# main1.net
KiCad netlist of a schematic drawn in EAGLE
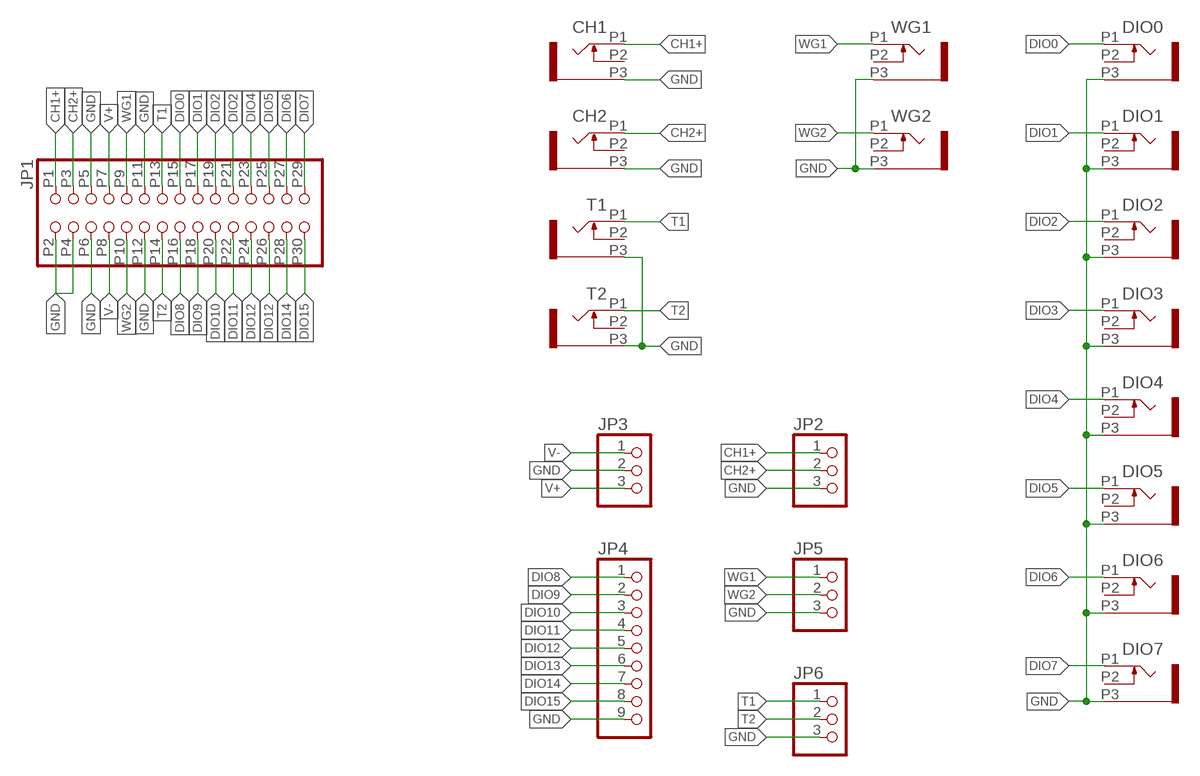
[diagram p0: schematic, sheet 1]

(export (version "E")
  (design (tool "Eeschema 10.0.6"))
  (components
    (comp (ref "CH1")
      (value "THONKICONN")
      (footprint "eagle-import:WQP-PJ301M-12_JACK")
      (libsource (lib "eagle-import") (part "THONKICONN"))
    )
    (comp (ref "CH2")
      (value "THONKICONN")
      (footprint "eagle-import:WQP-PJ301M-12_JACK")
      (libsource (lib "eagle-import") (part "THONKICONN"))
    )
    (comp (ref "DIO0")
      (value "THONKICONN")
      (footprint "eagle-import:WQP-PJ301M-12_JACK")
      (libsource (lib "eagle-import") (part "THONKICONN"))
    )
    (comp (ref "DIO1")
      (value "THONKICONN")
      (footprint "eagle-import:WQP-PJ301M-12_JACK")
      (libsource (lib "eagle-import") (part "THONKICONN"))
    )
    (comp (ref "DIO2")
      (value "THONKICONN")
      (footprint "eagle-import:WQP-PJ301M-12_JACK")
      (libsource (lib "eagle-import") (part "THONKICONN"))
    )
    (comp (ref "DIO3")
      (value "THONKICONN")
      (footprint "eagle-import:WQP-PJ301M-12_JACK")
      (libsource (lib "eagle-import") (part "THONKICONN"))
    )
    (comp (ref "DIO4")
      (value "THONKICONN")
      (footprint "eagle-import:WQP-PJ301M-12_JACK")
      (libsource (lib "eagle-import") (part "THONKICONN"))
    )
    (comp (ref "DIO5")
      (value "THONKICONN")
      (footprint "eagle-import:WQP-PJ301M-12_JACK")
      (libsource (lib "eagle-import") (part "THONKICONN"))
    )
    (comp (ref "DIO6")
      (value "THONKICONN")
      (footprint "eagle-import:WQP-PJ301M-12_JACK")
      (libsource (lib "eagle-import") (part "THONKICONN"))
    )
    (comp (ref "DIO7")
      (value "THONKICONN")
      (footprint "eagle-import:WQP-PJ301M-12_JACK")
      (libsource (lib "eagle-import") (part "THONKICONN"))
    )
    (comp (ref "JP1")
      (value "PINHD-2X15")
      (footprint "eagle-import:2X15_EDGE")
      (libsource (lib "eagle-import") (part "PINHD-2X15"))
    )
    (comp (ref "JP2")
      (value "PINHD-1X3/OCT")
      (footprint "eagle-import:1X03_OCT")
      (libsource (lib "eagle-import") (part "PINHD-1X3/OCT"))
    )
    (comp (ref "JP3")
      (value "PINHD-1X3/OCT")
      (footprint "eagle-import:1X03_OCT")
      (libsource (lib "eagle-import") (part "PINHD-1X3/OCT"))
    )
    (comp (ref "JP4")
      (value "PINHD-1X9/OCT")
      (footprint "eagle-import:1X09_OCT")
      (libsource (lib "eagle-import") (part "PINHD-1X9/OCT"))
    )
    (comp (ref "JP5")
      (value "PINHD-1X3/OCT")
      (footprint "eagle-import:1X03_OCT")
      (libsource (lib "eagle-import") (part "PINHD-1X3/OCT"))
    )
    (comp (ref "JP6")
      (value "PINHD-1X3/OCT")
      (footprint "eagle-import:1X03_OCT")
      (libsource (lib "eagle-import") (part "PINHD-1X3/OCT"))
    )
    (comp (ref "T1")
      (value "THONKICONN")
      (footprint "eagle-import:WQP-PJ301M-12_JACK")
      (libsource (lib "eagle-import") (part "THONKICONN"))
    )
    (comp (ref "T2")
      (value "THONKICONN")
      (footprint "eagle-import:WQP-PJ301M-12_JACK")
      (libsource (lib "eagle-import") (part "THONKICONN"))
    )
    (comp (ref "WG1")
      (value "THONKICONN")
      (footprint "eagle-import:WQP-PJ301M-12_JACK")
      (libsource (lib "eagle-import") (part "THONKICONN"))
    )
    (comp (ref "WG2")
      (value "THONKICONN")
      (footprint "eagle-import:WQP-PJ301M-12_JACK")
      (libsource (lib "eagle-import") (part "THONKICONN"))
    )
  )
  (nets
    (net (code "1") (name "CH1+") (class "Default")
      (node (ref "CH1") (pin "P1") (pinfunction "2_P1") (pintype "passive"))
      (node (ref "JP1") (pin "P1") (pinfunction "1_P1") (pintype "passive"))
      (node (ref "JP2") (pin "1") (pinfunction "1_1") (pintype "passive"))
    )
    (net (code "2") (name "CH2+") (class "Default")
      (node (ref "CH2") (pin "P1") (pinfunction "2_P1") (pintype "passive"))
      (node (ref "JP1") (pin "P3") (pinfunction "3_P3") (pintype "passive"))
      (node (ref "JP2") (pin "2") (pinfunction "2_2") (pintype "passive"))
    )
    (net (code "3") (name "DIO0") (class "Default")
      (node (ref "DIO0") (pin "P1") (pinfunction "2_P1") (pintype "passive"))
      (node (ref "JP1") (pin "P15") (pinfunction "15_P15") (pintype "passive"))
    )
    (net (code "4") (name "DIO1") (class "Default")
      (node (ref "DIO1") (pin "P1") (pinfunction "2_P1") (pintype "passive"))
      (node (ref "JP1") (pin "P17") (pinfunction "17_P17") (pintype "passive"))
    )
    (net (code "5") (name "DIO2") (class "Default")
      (node (ref "DIO2") (pin "P1") (pinfunction "2_P1") (pintype "passive"))
      (node (ref "JP1") (pin "P19") (pinfunction "19_P19") (pintype "passive"))
    )
    (net (code "6") (name "DIO3") (class "Default")
      (node (ref "DIO3") (pin "P1") (pinfunction "2_P1") (pintype "passive"))
      (node (ref "JP1") (pin "P21") (pinfunction "21_P21") (pintype "passive"))
    )
    (net (code "7") (name "DIO4") (class "Default")
      (node (ref "DIO4") (pin "P1") (pinfunction "2_P1") (pintype "passive"))
      (node (ref "JP1") (pin "P23") (pinfunction "23_P23") (pintype "passive"))
    )
    (net (code "8") (name "DIO5") (class "Default")
      (node (ref "DIO5") (pin "P1") (pinfunction "2_P1") (pintype "passive"))
      (node (ref "JP1") (pin "P25") (pinfunction "25_P25") (pintype "passive"))
    )
    (net (code "9") (name "DIO6") (class "Default")
      (node (ref "DIO6") (pin "P1") (pinfunction "2_P1") (pintype "passive"))
      (node (ref "JP1") (pin "P27") (pinfunction "27_P27") (pintype "passive"))
    )
    (net (code "10") (name "DIO7") (class "Default")
      (node (ref "DIO7") (pin "P1") (pinfunction "2_P1") (pintype "passive"))
      (node (ref "JP1") (pin "P29") (pinfunction "29_P29") (pintype "passive"))
    )
    (net (code "11") (name "DIO8") (class "Default")
      (node (ref "JP1") (pin "P16") (pinfunction "16_P16") (pintype "passive"))
      (node (ref "JP4") (pin "1") (pinfunction "1_1") (pintype "passive"))
    )
    (net (code "12") (name "DIO9") (class "Default")
      (node (ref "JP1") (pin "P18") (pinfunction "18_P18") (pintype "passive"))
      (node (ref "JP4") (pin "2") (pinfunction "2_2") (pintype "passive"))
    )
    (net (code "13") (name "DIO10") (class "Default")
      (node (ref "JP1") (pin "P20") (pinfunction "20_P20") (pintype "passive"))
      (node (ref "JP4") (pin "3") (pinfunction "3_3") (pintype "passive"))
    )
    (net (code "14") (name "DIO11") (class "Default")
      (node (ref "JP1") (pin "P22") (pinfunction "22_P22") (pintype "passive"))
      (node (ref "JP4") (pin "4") (pinfunction "4_4") (pintype "passive"))
    )
    (net (code "15") (name "DIO12") (class "Default")
      (node (ref "JP1") (pin "P24") (pinfunction "24_P24") (pintype "passive"))
      (node (ref "JP4") (pin "5") (pinfunction "5_5") (pintype "passive"))
    )
    (net (code "16") (name "DIO13") (class "Default")
      (node (ref "JP1") (pin "P26") (pinfunction "26_P26") (pintype "passive"))
      (node (ref "JP4") (pin "6") (pinfunction "6_6") (pintype "passive"))
    )
    (net (code "17") (name "DIO14") (class "Default")
      (node (ref "JP1") (pin "P28") (pinfunction "28_P28") (pintype "passive"))
      (node (ref "JP4") (pin "7") (pinfunction "7_7") (pintype "passive"))
    )
    (net (code "18") (name "DIO15") (class "Default")
      (node (ref "JP1") (pin "P30") (pinfunction "30_P30") (pintype "passive"))
      (node (ref "JP4") (pin "8") (pinfunction "8_8") (pintype "passive"))
    )
    (net (code "19") (name "GND") (class "Default")
      (node (ref "CH1") (pin "P3") (pinfunction "1_P3") (pintype "passive"))
      (node (ref "CH2") (pin "P3") (pinfunction "1_P3") (pintype "passive"))
      (node (ref "DIO0") (pin "P3") (pinfunction "1_P3") (pintype "passive"))
      (node (ref "DIO1") (pin "P3") (pinfunction "1_P3") (pintype "passive"))
      (node (ref "DIO2") (pin "P3") (pinfunction "1_P3") (pintype "passive"))
      (node (ref "DIO3") (pin "P3") (pinfunction "1_P3") (pintype "passive"))
      (node (ref "DIO4") (pin "P3") (pinfunction "1_P3") (pintype "passive"))
      (node (ref "DIO5") (pin "P3") (pinfunction "1_P3") (pintype "passive"))
      (node (ref "DIO6") (pin "P3") (pinfunction "1_P3") (pintype "passive"))
      (node (ref "DIO7") (pin "P3") (pinfunction "1_P3") (pintype "passive"))
      (node (ref "JP1") (pin "P11") (pinfunction "11_P11") (pintype "passive"))
      (node (ref "JP1") (pin "P12") (pinfunction "12_P12") (pintype "passive"))
      (node (ref "JP1") (pin "P2") (pinfunction "2_P2") (pintype "passive"))
      (node (ref "JP1") (pin "P4") (pinfunction "4_P4") (pintype "passive"))
      (node (ref "JP1") (pin "P5") (pinfunction "5_P5") (pintype "passive"))
      (node (ref "JP1") (pin "P6") (pinfunction "6_P6") (pintype "passive"))
      (node (ref "JP2") (pin "3") (pinfunction "3_3") (pintype "passive"))
      (node (ref "JP3") (pin "2") (pinfunction "2_2") (pintype "passive"))
      (node (ref "JP4") (pin "9") (pinfunction "9_9") (pintype "passive"))
      (node (ref "JP5") (pin "3") (pinfunction "3_3") (pintype "passive"))
      (node (ref "JP6") (pin "3") (pinfunction "3_3") (pintype "passive"))
      (node (ref "T1") (pin "P3") (pinfunction "1_P3") (pintype "passive"))
      (node (ref "T2") (pin "P3") (pinfunction "1_P3") (pintype "passive"))
      (node (ref "WG1") (pin "P3") (pinfunction "1_P3") (pintype "passive"))
      (node (ref "WG2") (pin "P3") (pinfunction "1_P3") (pintype "passive"))
    )
    (net (code "20") (name "T1") (class "Default")
      (node (ref "JP1") (pin "P13") (pinfunction "13_P13") (pintype "passive"))
      (node (ref "JP6") (pin "1") (pinfunction "1_1") (pintype "passive"))
      (node (ref "T1") (pin "P1") (pinfunction "2_P1") (pintype "passive"))
    )
    (net (code "21") (name "T2") (class "Default")
      (node (ref "JP1") (pin "P14") (pinfunction "14_P14") (pintype "passive"))
      (node (ref "JP6") (pin "2") (pinfunction "2_2") (pintype "passive"))
      (node (ref "T2") (pin "P1") (pinfunction "2_P1") (pintype "passive"))
    )
    (net (code "22") (name "V+") (class "Default")
      (node (ref "JP1") (pin "P7") (pinfunction "7_P7") (pintype "passive"))
      (node (ref "JP3") (pin "3") (pinfunction "3_3") (pintype "passive"))
    )
    (net (code "23") (name "V-") (class "Default")
      (node (ref "JP1") (pin "P8") (pinfunction "8_P8") (pintype "passive"))
      (node (ref "JP3") (pin "1") (pinfunction "1_1") (pintype "passive"))
    )
    (net (code "24") (name "WG1") (class "Default")
      (node (ref "JP1") (pin "P9") (pinfunction "9_P9") (pintype "passive"))
      (node (ref "JP5") (pin "1") (pinfunction "1_1") (pintype "passive"))
      (node (ref "WG1") (pin "P1") (pinfunction "2_P1") (pintype "passive"))
    )
    (net (code "25") (name "WG2") (class "Default")
      (node (ref "JP1") (pin "P10") (pinfunction "10_P10") (pintype "passive"))
      (node (ref "JP5") (pin "2") (pinfunction "2_2") (pintype "passive"))
      (node (ref "WG2") (pin "P1") (pinfunction "2_P1") (pintype "passive"))
    )
    (net (code "26") (name "unconnected-(CH1-3-PadP2)") (class "Default")
      (node (ref "CH1") (pin "P2") (pinfunction "3_P2") (pintype "passive"))
    )
    (net (code "27") (name "unconnected-(CH2-3-PadP2)") (class "Default")
      (node (ref "CH2") (pin "P2") (pinfunction "3_P2") (pintype "passive"))
    )
    (net (code "28") (name "unconnected-(DIO0-3-PadP2)") (class "Default")
      (node (ref "DIO0") (pin "P2") (pinfunction "3_P2") (pintype "passive"))
    )
    (net (code "29") (name "unconnected-(DIO1-3-PadP2)") (class "Default")
      (node (ref "DIO1") (pin "P2") (pinfunction "3_P2") (pintype "passive"))
    )
    (net (code "30") (name "unconnected-(DIO2-3-PadP2)") (class "Default")
      (node (ref "DIO2") (pin "P2") (pinfunction "3_P2") (pintype "passive"))
    )
    (net (code "31") (name "unconnected-(DIO3-3-PadP2)") (class "Default")
      (node (ref "DIO3") (pin "P2") (pinfunction "3_P2") (pintype "passive"))
    )
    (net (code "32") (name "unconnected-(DIO4-3-PadP2)") (class "Default")
      (node (ref "DIO4") (pin "P2") (pinfunction "3_P2") (pintype "passive"))
    )
    (net (code "33") (name "unconnected-(DIO5-3-PadP2)") (class "Default")
      (node (ref "DIO5") (pin "P2") (pinfunction "3_P2") (pintype "passive"))
    )
    (net (code "34") (name "unconnected-(DIO6-3-PadP2)") (class "Default")
      (node (ref "DIO6") (pin "P2") (pinfunction "3_P2") (pintype "passive"))
    )
    (net (code "35") (name "unconnected-(DIO7-3-PadP2)") (class "Default")
      (node (ref "DIO7") (pin "P2") (pinfunction "3_P2") (pintype "passive"))
    )
    (net (code "36") (name "unconnected-(T1-3-PadP2)") (class "Default")
      (node (ref "T1") (pin "P2") (pinfunction "3_P2") (pintype "passive"))
    )
    (net (code "37") (name "unconnected-(T2-3-PadP2)") (class "Default")
      (node (ref "T2") (pin "P2") (pinfunction "3_P2") (pintype "passive"))
    )
    (net (code "38") (name "unconnected-(WG1-3-PadP2)") (class "Default")
      (node (ref "WG1") (pin "P2") (pinfunction "3_P2") (pintype "passive"))
    )
    (net (code "39") (name "unconnected-(WG2-3-PadP2)") (class "Default")
      (node (ref "WG2") (pin "P2") (pinfunction "3_P2") (pintype "passive"))
    )
  )
)
